# Adafruit_Feather_M0_Adalogger.net
KiCad netlist of a schematic drawn in EAGLE
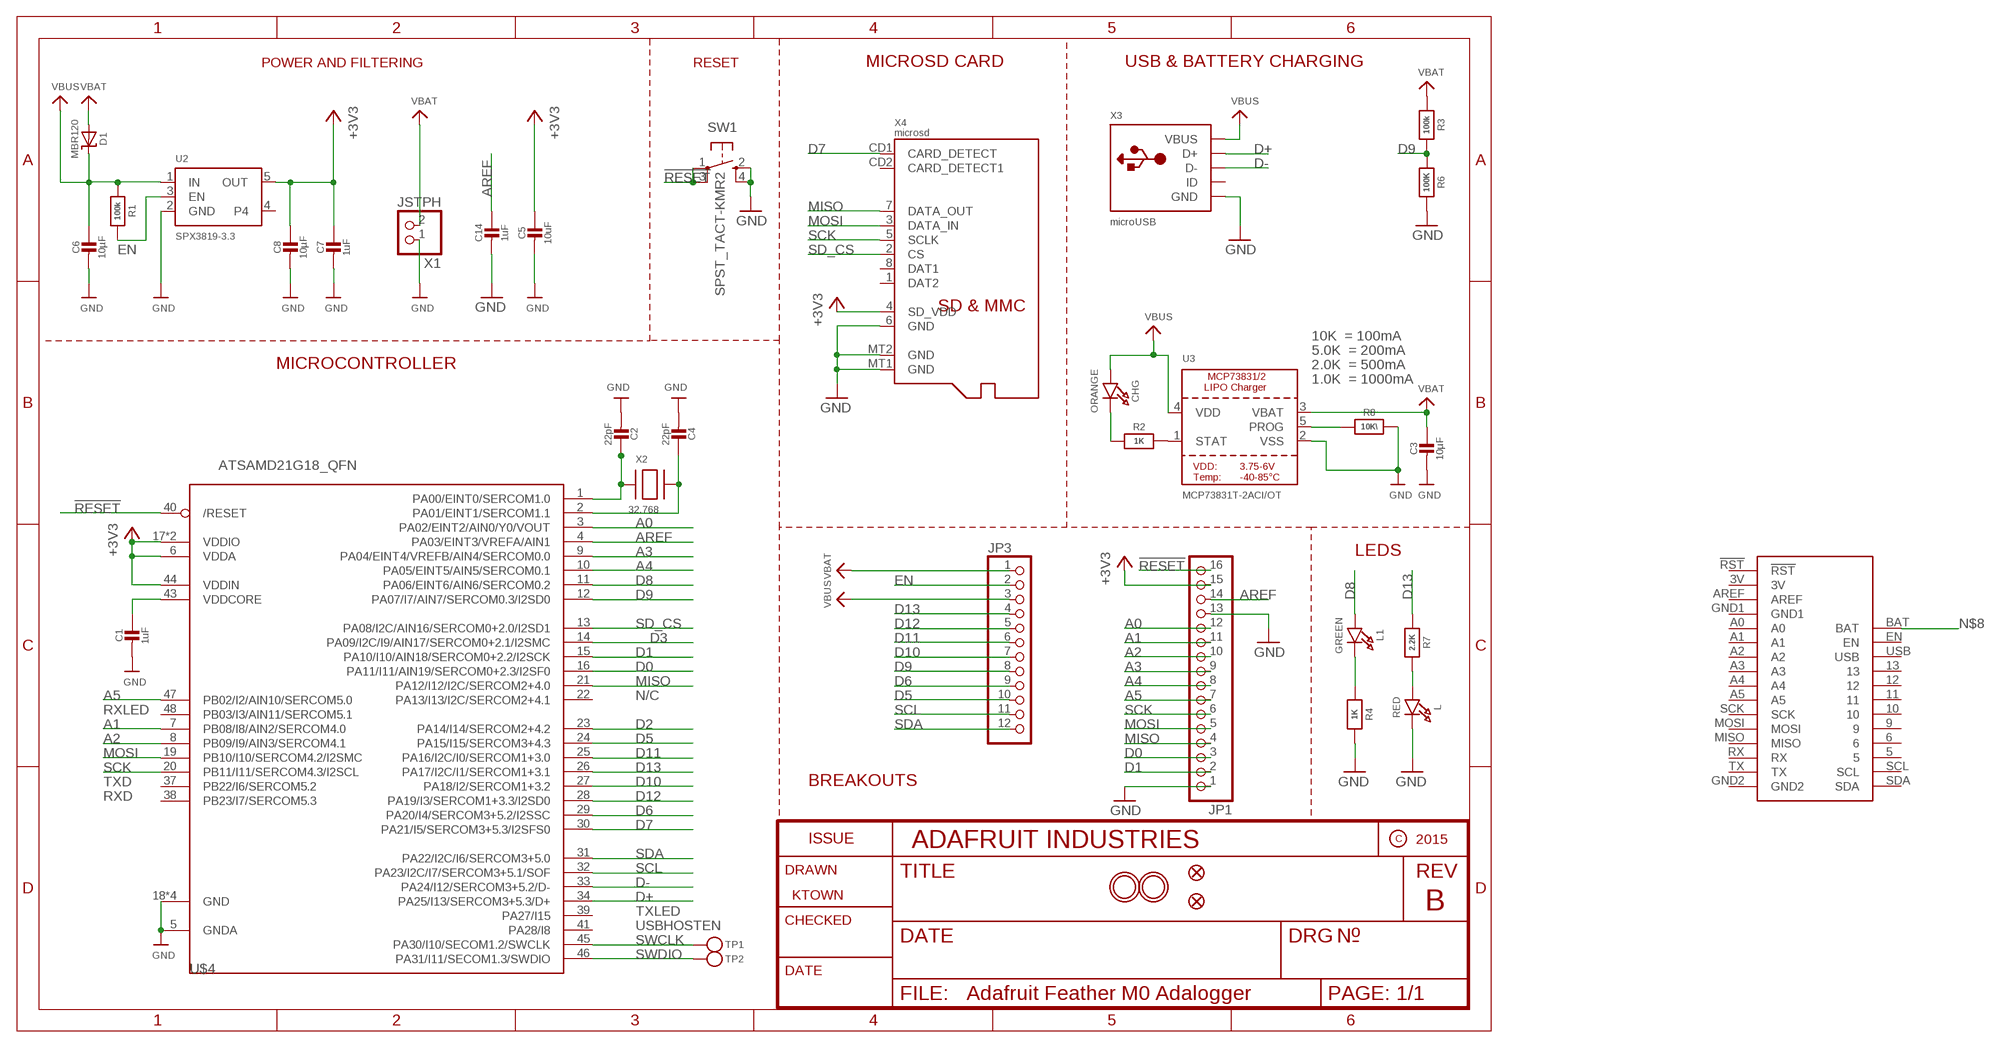
[diagram p0: schematic, sheet 1]

(export (version "E")
  (design (tool "Eeschema 10.0.6"))
  (components
    (comp (ref "C1")
      (value "1uF")
      (footprint "eagle-import:0603-NO")
      (libsource (lib "eagle-import") (part "CAP_CERAMIC0603_NO"))
    )
    (comp (ref "C2")
      (value "22pF")
      (footprint "eagle-import:0603-NO")
      (libsource (lib "eagle-import") (part "CAP_CERAMIC0603_NO"))
    )
    (comp (ref "C3")
      (value "10µF")
      (footprint "eagle-import:0805-NO")
      (libsource (lib "eagle-import") (part "CAP_CERAMIC0805-NOOUTLINE"))
    )
    (comp (ref "C4")
      (value "22pF")
      (footprint "eagle-import:0603-NO")
      (libsource (lib "eagle-import") (part "CAP_CERAMIC0603_NO"))
    )
    (comp (ref "C5")
      (value "10uF")
      (footprint "eagle-import:0805-NO")
      (libsource (lib "eagle-import") (part "CAP_CERAMIC0805-NOOUTLINE"))
    )
    (comp (ref "C6")
      (value "10µF")
      (footprint "eagle-import:0805-NO")
      (libsource (lib "eagle-import") (part "CAP_CERAMIC0805-NOOUTLINE"))
    )
    (comp (ref "C7")
      (value "1uF")
      (footprint "eagle-import:0603-NO")
      (libsource (lib "eagle-import") (part "CAP_CERAMIC0603_NO"))
    )
    (comp (ref "C8")
      (value "10µF")
      (footprint "eagle-import:0805-NO")
      (libsource (lib "eagle-import") (part "CAP_CERAMIC0805-NOOUTLINE"))
    )
    (comp (ref "C14")
      (value "1uF")
      (footprint "eagle-import:0603-NO")
      (libsource (lib "eagle-import") (part "CAP_CERAMIC0603_NO"))
    )
    (comp (ref "CHG")
      (value "ORANGE")
      (footprint "eagle-import:CHIPLED_0805_NOOUTLINE")
      (libsource (lib "eagle-import") (part "LED0805_NOOUTLINE"))
    )
    (comp (ref "D1")
      (value "MBR120")
      (footprint "eagle-import:SOD-123")
      (libsource (lib "eagle-import") (part "DIODE-SCHOTTKYSOD-123"))
    )
    (comp (ref "JP1")
      (value "HEADER-1X16ROUND")
      (footprint "eagle-import:1X16_ROUND")
      (libsource (lib "eagle-import") (part "HEADER-1X16ROUND"))
    )
    (comp (ref "JP3")
      (value "HEADER-1X12")
      (footprint "eagle-import:1X12_ROUND")
      (libsource (lib "eagle-import") (part "HEADER-1X12"))
    )
    (comp (ref "L")
      (value "RED")
      (footprint "eagle-import:CHIPLED_0805_NOOUTLINE")
      (libsource (lib "eagle-import") (part "LED0805_NOOUTLINE"))
    )
    (comp (ref "L1")
      (value "GREEN")
      (footprint "eagle-import:CHIPLED_0805_NOOUTLINE")
      (libsource (lib "eagle-import") (part "LED0805_NOOUTLINE"))
    )
    (comp (ref "R1")
      (value "100k")
      (footprint "eagle-import:0603-NO")
      (libsource (lib "eagle-import") (part "RESISTOR_0603_NOOUT"))
    )
    (comp (ref "R2")
      (value "1K")
      (footprint "eagle-import:0603-NO")
      (libsource (lib "eagle-import") (part "RESISTOR_0603_NOOUT"))
    )
    (comp (ref "R3")
      (value "100k")
      (footprint "eagle-import:0603-NO")
      (libsource (lib "eagle-import") (part "RESISTOR_0603_NOOUT"))
    )
    (comp (ref "R4")
      (value "1K")
      (footprint "eagle-import:0603-NO")
      (libsource (lib "eagle-import") (part "RESISTOR_0603_NOOUT"))
    )
    (comp (ref "R6")
      (value "100K")
      (footprint "eagle-import:0603-NO")
      (libsource (lib "eagle-import") (part "RESISTOR_0603_NOOUT"))
    )
    (comp (ref "R7")
      (value "2.2K")
      (footprint "eagle-import:0603-NO")
      (libsource (lib "eagle-import") (part "RESISTOR_0603_NOOUT"))
    )
    (comp (ref "R8")
      (value "10K\\")
      (footprint "eagle-import:0603-NO")
      (libsource (lib "eagle-import") (part "RESISTOR_0603_NOOUT"))
    )
    (comp (ref "SW1")
      (value "SPST_TACT-KMR2")
      (footprint "eagle-import:KMR2")
      (libsource (lib "eagle-import") (part "SPST_TACT-KMR2"))
    )
    (comp (ref "TP1")
      (value "TESTPOINTROUND1.5MM")
      (footprint "eagle-import:TESTPOINT_ROUND_1.5MM")
      (libsource (lib "eagle-import") (part "TESTPOINTROUND1.5MM"))
    )
    (comp (ref "TP2")
      (value "TESTPOINTROUND1.5MM")
      (footprint "eagle-import:TESTPOINT_ROUND_1.5MM")
      (libsource (lib "eagle-import") (part "TESTPOINTROUND1.5MM"))
    )
    (comp (ref "U$4")
      (value "ATSAMD21G18_QFN")
      (footprint "eagle-import:TQFN48_7MM")
      (libsource (lib "eagle-import") (part "ATSAMD21J_QFN"))
    )
    (comp (ref "U$12")
      (value "FEATHER_MO_ADALOGGER")
      (footprint "eagle-import:FEATHER_M0_ADALOGGER")
      (libsource (lib "eagle-import") (part "FEATHER_MO_ADALOGGER"))
    )
    (comp (ref "U$31")
      (value "MOUNTINGHOLE2.5")
      (footprint "eagle-import:MOUNTINGHOLE_2.5_PLATED")
      (libsource (lib "eagle-import") (part "MOUNTINGHOLE2.5"))
    )
    (comp (ref "U$32")
      (value "MOUNTINGHOLE2.5")
      (footprint "eagle-import:MOUNTINGHOLE_2.5_PLATED")
      (libsource (lib "eagle-import") (part "MOUNTINGHOLE2.5"))
    )
    (comp (ref "U$34")
      (value "FIDUCIAL\"\"")
      (footprint "eagle-import:FIDUCIAL_1MM")
      (libsource (lib "eagle-import") (part "FIDUCIAL{dblquote}{dblquote}"))
    )
    (comp (ref "U$35")
      (value "FIDUCIAL\"\"")
      (footprint "eagle-import:FIDUCIAL_1MM")
      (libsource (lib "eagle-import") (part "FIDUCIAL{dblquote}{dblquote}"))
    )
    (comp (ref "U2")
      (value "SPX3819-3.3")
      (footprint "eagle-import:SOT23-5")
      (libsource (lib "eagle-import") (part "VREG_SOT23-5"))
    )
    (comp (ref "U3")
      (value "MCP73831T-2ACI/OT")
      (footprint "eagle-import:SOT23-5")
      (libsource (lib "eagle-import") (part "MCP73831/2"))
    )
    (comp (ref "X1")
      (value "JSTPH")
      (footprint "eagle-import:JSTPH2")
      (libsource (lib "eagle-import") (part "CON_JST_PH_2PIN"))
    )
    (comp (ref "X2")
      (value "32.768")
      (footprint "eagle-import:XTAL3215")
      (libsource (lib "eagle-import") (part "XTAL-3.2X1.5"))
    )
    (comp (ref "X3")
      (value "microUSB")
      (footprint "eagle-import:4UCONN_20329_V2")
      (libsource (lib "eagle-import") (part "USB_MICRO_20329_V2"))
    )
    (comp (ref "X4")
      (value "microsd")
      (footprint "eagle-import:MICROSD")
      (libsource (lib "eagle-import") (part "MICROSD"))
    )
  )
  (nets
    (net (code "1") (name "+3V3") (class "Default")
      (node (ref "C5") (pin "1") (pinfunction "1_1") (pintype "passive"))
      (node (ref "C7") (pin "1") (pinfunction "1_1") (pintype "passive"))
      (node (ref "C8") (pin "1") (pinfunction "1_1") (pintype "passive"))
      (node (ref "JP1") (pin "15") (pinfunction "15_15") (pintype "passive"))
      (node (ref "U$4") (pin "17") (pinfunction "VDDIO_17") (pintype "power_in"))
      (node (ref "U$4") (pin "36") (pinfunction "VDDIO_36") (pintype "power_in"))
      (node (ref "U$4") (pin "44") (pinfunction "VDDIN_44") (pintype "power_in"))
      (node (ref "U$4") (pin "6") (pinfunction "VDDA_6") (pintype "power_in"))
      (node (ref "U2") (pin "5") (pinfunction "OUT_5") (pintype "power_in"))
      (node (ref "X4") (pin "4") (pinfunction "SD_VDD_4") (pintype "power_in"))
    )
    (net (code "2") (name "/A0") (class "Default")
      (node (ref "JP1") (pin "12") (pinfunction "12_12") (pintype "passive"))
      (node (ref "U$4") (pin "3") (pinfunction "PA02/EINT2/AIN0/Y0/VOUT_3") (pintype "bidirectional"))
    )
    (net (code "3") (name "/A1") (class "Default")
      (node (ref "JP1") (pin "11") (pinfunction "11_11") (pintype "passive"))
      (node (ref "U$4") (pin "7") (pinfunction "PB08/I8/AIN2/SERCOM4.0_7") (pintype "bidirectional"))
    )
    (net (code "4") (name "/A2") (class "Default")
      (node (ref "JP1") (pin "10") (pinfunction "10_10") (pintype "passive"))
      (node (ref "U$4") (pin "8") (pinfunction "PB09/I9/AIN3/SERCOM4.1_8") (pintype "bidirectional"))
    )
    (net (code "5") (name "/A3") (class "Default")
      (node (ref "JP1") (pin "9") (pinfunction "9_9") (pintype "passive"))
      (node (ref "U$4") (pin "9") (pinfunction "PA04/EINT4/VREFB/AIN4/SERCOM0.0_9") (pintype "bidirectional"))
    )
    (net (code "6") (name "/A4") (class "Default")
      (node (ref "JP1") (pin "8") (pinfunction "8_8") (pintype "passive"))
      (node (ref "U$4") (pin "10") (pinfunction "PA05/EINT5/AIN5/SERCOM0.1_10") (pintype "bidirectional"))
    )
    (net (code "7") (name "/A5") (class "Default")
      (node (ref "JP1") (pin "7") (pinfunction "7_7") (pintype "passive"))
      (node (ref "U$4") (pin "47") (pinfunction "PB02/I2/AIN10/SERCOM5.0_47") (pintype "bidirectional"))
    )
    (net (code "8") (name "/AREF") (class "Default")
      (node (ref "C14") (pin "1") (pinfunction "1_1") (pintype "passive"))
      (node (ref "JP1") (pin "14") (pinfunction "14_14") (pintype "passive"))
      (node (ref "U$4") (pin "4") (pinfunction "PA03/EINT3/VREFA/AIN1_4") (pintype "bidirectional"))
    )
    (net (code "9") (name "/D+") (class "Default")
      (node (ref "U$4") (pin "34") (pinfunction "PA25/I13/SERCOM3+5.3/D+_34") (pintype "bidirectional"))
      (node (ref "X3") (pin "D+") (pinfunction "D+_D+") (pintype "bidirectional"))
    )
    (net (code "10") (name "/D-") (class "Default")
      (node (ref "U$4") (pin "33") (pinfunction "PA24/I12/SERCOM3+5.2/D-_33") (pintype "bidirectional"))
      (node (ref "X3") (pin "D-") (pinfunction "D-_D-") (pintype "bidirectional"))
    )
    (net (code "11") (name "/D0") (class "Default")
      (node (ref "JP1") (pin "3") (pinfunction "3_3") (pintype "passive"))
      (node (ref "U$4") (pin "16") (pinfunction "PA11/I11/AIN19/SERCOM0+2.3/I2SF0_16") (pintype "bidirectional"))
    )
    (net (code "12") (name "/D1") (class "Default")
      (node (ref "JP1") (pin "2") (pinfunction "2_2") (pintype "passive"))
      (node (ref "U$4") (pin "15") (pinfunction "PA10/I10/AIN18/SERCOM0+2.2/I2SCK_15") (pintype "bidirectional"))
    )
    (net (code "13") (name "/D2") (class "Default")
      (node (ref "U$4") (pin "23") (pinfunction "PA14/I14/SERCOM2+4.2_23") (pintype "bidirectional"))
    )
    (net (code "14") (name "/D3") (class "Default")
      (node (ref "U$4") (pin "14") (pinfunction "PA09/I2C/I9/AIN17/SERCOM0+2.1/I2SMC_14") (pintype "bidirectional"))
    )
    (net (code "15") (name "/D5") (class "Default")
      (node (ref "JP3") (pin "10") (pinfunction "10_10") (pintype "passive"))
      (node (ref "U$4") (pin "24") (pinfunction "PA15/I15/SERCOM3+4.3_24") (pintype "bidirectional"))
    )
    (net (code "16") (name "/D6") (class "Default")
      (node (ref "JP3") (pin "9") (pinfunction "9_9") (pintype "passive"))
      (node (ref "U$4") (pin "29") (pinfunction "PA20/I4/SERCOM3+5.2/I2SSC_29") (pintype "bidirectional"))
    )
    (net (code "17") (name "/D7") (class "Default")
      (node (ref "U$4") (pin "30") (pinfunction "PA21/I5/SERCOM3+5.3/I2SFS0_30") (pintype "bidirectional"))
      (node (ref "X4") (pin "CD1") (pinfunction "CARD_DETECT_CD1") (pintype "passive"))
    )
    (net (code "18") (name "/D8") (class "Default")
      (node (ref "L1") (pin "A") (pinfunction "A_A") (pintype "passive"))
      (node (ref "U$4") (pin "11") (pinfunction "PA06/EINT6/AIN6/SERCOM0.2_11") (pintype "bidirectional"))
    )
    (net (code "19") (name "/D9") (class "Default")
      (node (ref "JP3") (pin "8") (pinfunction "8_8") (pintype "passive"))
      (node (ref "R3") (pin "2") (pinfunction "2_2") (pintype "passive"))
      (node (ref "R6") (pin "1") (pinfunction "1_1") (pintype "passive"))
      (node (ref "U$4") (pin "12") (pinfunction "PA07/I7/AIN7/SERCOM0.3/I2SD0_12") (pintype "bidirectional"))
    )
    (net (code "20") (name "/D10") (class "Default")
      (node (ref "JP3") (pin "7") (pinfunction "7_7") (pintype "passive"))
      (node (ref "U$4") (pin "27") (pinfunction "PA18/I2/SERCOM1+3.2_27") (pintype "bidirectional"))
    )
    (net (code "21") (name "/D11") (class "Default")
      (node (ref "JP3") (pin "6") (pinfunction "6_6") (pintype "passive"))
      (node (ref "U$4") (pin "25") (pinfunction "PA16/I2C/I0/SERCOM1+3.0_25") (pintype "bidirectional"))
    )
    (net (code "22") (name "/D12") (class "Default")
      (node (ref "JP3") (pin "5") (pinfunction "5_5") (pintype "passive"))
      (node (ref "U$4") (pin "28") (pinfunction "PA19/I3/SERCOM1+3.3/I2SD0_28") (pintype "bidirectional"))
    )
    (net (code "23") (name "/D13") (class "Default")
      (node (ref "JP3") (pin "4") (pinfunction "4_4") (pintype "passive"))
      (node (ref "R7") (pin "1") (pinfunction "1_1") (pintype "passive"))
      (node (ref "U$4") (pin "26") (pinfunction "PA17/I2C/I1/SERCOM1+3.1_26") (pintype "bidirectional"))
    )
    (net (code "24") (name "/EN") (class "Default")
      (node (ref "JP3") (pin "2") (pinfunction "2_2") (pintype "passive"))
      (node (ref "R1") (pin "2") (pinfunction "2_2") (pintype "passive"))
      (node (ref "U2") (pin "3") (pinfunction "EN_3") (pintype "input"))
    )
    (net (code "25") (name "/MISO") (class "Default")
      (node (ref "JP1") (pin "4") (pinfunction "4_4") (pintype "passive"))
      (node (ref "U$4") (pin "21") (pinfunction "PA12/I12/I2C/SERCOM2+4.0_21") (pintype "bidirectional"))
      (node (ref "X4") (pin "7") (pinfunction "DATA_OUT_7") (pintype "output"))
    )
    (net (code "26") (name "/MOSI") (class "Default")
      (node (ref "JP1") (pin "5") (pinfunction "5_5") (pintype "passive"))
      (node (ref "U$4") (pin "19") (pinfunction "PB10/I10/SERCOM4.2/I2SMC_19") (pintype "bidirectional"))
      (node (ref "X4") (pin "3") (pinfunction "DATA_IN_3") (pintype "input"))
    )
    (net (code "27") (name "/N$8") (class "Default")
      (node (ref "U$12") (pin "BAT") (pinfunction "BAT_BAT") (pintype "bidirectional"))
    )
    (net (code "28") (name "/SCK") (class "Default")
      (node (ref "JP1") (pin "6") (pinfunction "6_6") (pintype "passive"))
      (node (ref "U$4") (pin "20") (pinfunction "PB11/I11/SERCOM4.3/I2SCL_20") (pintype "bidirectional"))
      (node (ref "X4") (pin "5") (pinfunction "SCLK_5") (pintype "input"))
    )
    (net (code "29") (name "/SCL") (class "Default")
      (node (ref "JP3") (pin "11") (pinfunction "11_11") (pintype "passive"))
      (node (ref "U$4") (pin "32") (pinfunction "PA23/I2C/I7/SERCOM3+5.1/SOF_32") (pintype "bidirectional"))
    )
    (net (code "30") (name "/SDA") (class "Default")
      (node (ref "JP3") (pin "12") (pinfunction "12_12") (pintype "passive"))
      (node (ref "U$4") (pin "31") (pinfunction "PA22/I2C/I6/SERCOM3+5.0_31") (pintype "bidirectional"))
    )
    (net (code "31") (name "/SD_CS") (class "Default")
      (node (ref "U$4") (pin "13") (pinfunction "PA08/I2C/AIN16/SERCOM0+2.0/I2SD1_13") (pintype "bidirectional"))
      (node (ref "X4") (pin "2") (pinfunction "CS_2") (pintype "input"))
    )
    (net (code "32") (name "/SWCLK") (class "Default")
      (node (ref "TP1") (pin "P$1") (pinfunction "P$1_P$1") (pintype "bidirectional"))
      (node (ref "U$4") (pin "45") (pinfunction "PA30/I10/SECOM1.2/SWCLK_45") (pintype "bidirectional"))
    )
    (net (code "33") (name "/SWDIO") (class "Default")
      (node (ref "TP2") (pin "P$1") (pinfunction "P$1_P$1") (pintype "bidirectional"))
      (node (ref "U$4") (pin "46") (pinfunction "PA31/I11/SECOM1.3/SWDIO_46") (pintype "bidirectional"))
    )
    (net (code "34") (name "/~{RESET}") (class "Default")
      (node (ref "JP1") (pin "16") (pinfunction "16_16") (pintype "passive"))
      (node (ref "SW1") (pin "1") (pinfunction "P_1") (pintype "passive"))
      (node (ref "SW1") (pin "3") (pinfunction "P1_3") (pintype "passive"))
      (node (ref "U$4") (pin "40") (pinfunction "/RESET_40") (pintype "bidirectional"))
    )
    (net (code "35") (name "GND") (class "Default")
      (node (ref "C1") (pin "2") (pinfunction "2_2") (pintype "passive"))
      (node (ref "C14") (pin "2") (pinfunction "2_2") (pintype "passive"))
      (node (ref "C2") (pin "2") (pinfunction "2_2") (pintype "passive"))
      (node (ref "C3") (pin "2") (pinfunction "2_2") (pintype "passive"))
      (node (ref "C4") (pin "2") (pinfunction "2_2") (pintype "passive"))
      (node (ref "C5") (pin "2") (pinfunction "2_2") (pintype "passive"))
      (node (ref "C6") (pin "2") (pinfunction "2_2") (pintype "passive"))
      (node (ref "C7") (pin "2") (pinfunction "2_2") (pintype "passive"))
      (node (ref "C8") (pin "2") (pinfunction "2_2") (pintype "passive"))
      (node (ref "JP1") (pin "1") (pinfunction "1_1") (pintype "passive"))
      (node (ref "JP1") (pin "13") (pinfunction "13_13") (pintype "passive"))
      (node (ref "L") (pin "C") (pinfunction "C_C") (pintype "passive"))
      (node (ref "R4") (pin "2") (pinfunction "2_2") (pintype "passive"))
      (node (ref "R6") (pin "2") (pinfunction "2_2") (pintype "passive"))
      (node (ref "R8") (pin "2") (pinfunction "2_2") (pintype "passive"))
      (node (ref "SW1") (pin "2") (pinfunction "S_2") (pintype "passive"))
      (node (ref "SW1") (pin "4") (pinfunction "S1_4") (pintype "passive"))
      (node (ref "U$4") (pin "18") (pinfunction "GND_18") (pintype "power_in"))
      (node (ref "U$4") (pin "35") (pinfunction "GND_35") (pintype "power_in"))
      (node (ref "U$4") (pin "42") (pinfunction "GND_42") (pintype "power_in"))
      (node (ref "U$4") (pin "5") (pinfunction "GNDA_5") (pintype "power_in"))
      (node (ref "U$4") (pin "THERMAL") (pinfunction "GND_THERMAL") (pintype "power_in"))
      (node (ref "U2") (pin "2") (pinfunction "GND_2") (pintype "power_in"))
      (node (ref "U3") (pin "2") (pinfunction "VSS_2") (pintype "power_in"))
      (node (ref "X1") (pin "1") (pinfunction "1_1") (pintype "passive"))
      (node (ref "X3") (pin "BASE@1") (pinfunction "GND_BASE@1") (pintype "power_in"))
      (node (ref "X3") (pin "BASE@2") (pinfunction "GND_BASE@2") (pintype "power_in"))
      (node (ref "X3") (pin "GND") (pinfunction "GND_GND") (pintype "power_in"))
      (node (ref "X3") (pin "SPRT@1") (pinfunction "GND_SPRT@1") (pintype "power_in"))
      (node (ref "X3") (pin "SPRT@2") (pinfunction "GND_SPRT@2") (pintype "power_in"))
      (node (ref "X3") (pin "SPRT@3") (pinfunction "GND_SPRT@3") (pintype "power_in"))
      (node (ref "X3") (pin "SPRT@4") (pinfunction "GND_SPRT@4") (pintype "power_in"))
      (node (ref "X4") (pin "6") (pinfunction "GND_6") (pintype "power_in"))
      (node (ref "X4") (pin "MT1") (pinfunction "GND_MT1") (pintype "power_in"))
      (node (ref "X4") (pin "MT2") (pinfunction "GND_MT2") (pintype "power_in"))
    )
    (net (code "36") (name "Net-(CHG-PadC)") (class "Default")
      (node (ref "CHG") (pin "C") (pinfunction "C_C") (pintype "passive"))
      (node (ref "R2") (pin "1") (pinfunction "1_1") (pintype "passive"))
    )
    (net (code "37") (name "Net-(L-PadA)") (class "Default")
      (node (ref "L") (pin "A") (pinfunction "A_A") (pintype "passive"))
      (node (ref "R7") (pin "2") (pinfunction "2_2") (pintype "passive"))
    )
    (net (code "38") (name "Net-(L1-PadC)") (class "Default")
      (node (ref "L1") (pin "C") (pinfunction "C_C") (pintype "passive"))
      (node (ref "R4") (pin "1") (pinfunction "1_1") (pintype "passive"))
    )
    (net (code "39") (name "Net-(U$4-PA00{slash}EINT0{slash}SERCOM1.0)") (class "Default")
      (node (ref "C2") (pin "1") (pinfunction "1_1") (pintype "passive"))
      (node (ref "U$4") (pin "1") (pinfunction "PA00/EINT0/SERCOM1.0_1") (pintype "bidirectional"))
      (node (ref "X2") (pin "P$1") (pinfunction "P$1_P$1") (pintype "bidirectional"))
    )
    (net (code "40") (name "Net-(U$4-PA01{slash}EINT1{slash}SERCOM1.1)") (class "Default")
      (node (ref "C4") (pin "1") (pinfunction "1_1") (pintype "passive"))
      (node (ref "U$4") (pin "2") (pinfunction "PA01/EINT1/SERCOM1.1_2") (pintype "bidirectional"))
      (node (ref "X2") (pin "P$2") (pinfunction "P$2_P$2") (pintype "bidirectional"))
    )
    (net (code "41") (name "Net-(U$4-VDDCORE)") (class "Default")
      (node (ref "C1") (pin "1") (pinfunction "1_1") (pintype "passive"))
      (node (ref "U$4") (pin "43") (pinfunction "VDDCORE_43") (pintype "power_in"))
    )
    (net (code "42") (name "Net-(U3-PROG)") (class "Default")
      (node (ref "R8") (pin "1") (pinfunction "1_1") (pintype "passive"))
      (node (ref "U3") (pin "5") (pinfunction "PROG_5") (pintype "input"))
    )
    (net (code "43") (name "Net-(U3-STAT)") (class "Default")
      (node (ref "R2") (pin "2") (pinfunction "2_2") (pintype "passive"))
      (node (ref "U3") (pin "1") (pinfunction "STAT_1") (pintype "output"))
    )
    (net (code "44") (name "VBAT") (class "Default")
      (node (ref "C3") (pin "1") (pinfunction "1_1") (pintype "passive"))
      (node (ref "D1") (pin "A") (pinfunction "A_A") (pintype "passive"))
      (node (ref "JP3") (pin "1") (pinfunction "1_1") (pintype "passive"))
      (node (ref "R3") (pin "1") (pinfunction "1_1") (pintype "passive"))
      (node (ref "U3") (pin "3") (pinfunction "VBAT_3") (pintype "power_in"))
      (node (ref "X1") (pin "2") (pinfunction "2_2") (pintype "passive"))
    )
    (net (code "45") (name "VBUS") (class "Default")
      (node (ref "C6") (pin "1") (pinfunction "1_1") (pintype "passive"))
      (node (ref "CHG") (pin "A") (pinfunction "A_A") (pintype "passive"))
      (node (ref "D1") (pin "C") (pinfunction "C_C") (pintype "passive"))
      (node (ref "JP3") (pin "3") (pinfunction "3_3") (pintype "passive"))
      (node (ref "R1") (pin "1") (pinfunction "1_1") (pintype "passive"))
      (node (ref "U2") (pin "1") (pinfunction "IN_1") (pintype "power_in"))
      (node (ref "U3") (pin "4") (pinfunction "VDD_4") (pintype "power_in"))
      (node (ref "X3") (pin "VBUS") (pinfunction "VBUS_VBUS") (pintype "power_in"))
    )
    (net (code "46") (name "unconnected-(U$4-PA13{slash}I13{slash}I2C{slash}SERCOM2+4.1-Pad22)") (class "Default")
      (node (ref "U$4") (pin "22") (pinfunction "PA13/I13/I2C/SERCOM2+4.1_22") (pintype "bidirectional"))
    )
    (net (code "47") (name "unconnected-(U$4-PA27{slash}I15-Pad39)") (class "Default")
      (node (ref "U$4") (pin "39") (pinfunction "PA27/I15_39") (pintype "bidirectional"))
    )
    (net (code "48") (name "unconnected-(U$4-PA28{slash}I8-Pad41)") (class "Default")
      (node (ref "U$4") (pin "41") (pinfunction "PA28/I8_41") (pintype "bidirectional"))
    )
    (net (code "49") (name "unconnected-(U$4-PB03{slash}I3{slash}AIN11{slash}SERCOM5.1-Pad48)") (class "Default")
      (node (ref "U$4") (pin "48") (pinfunction "PB03/I3/AIN11/SERCOM5.1_48") (pintype "bidirectional"))
    )
    (net (code "50") (name "unconnected-(U$4-PB22{slash}I6{slash}SERCOM5.2-Pad37)") (class "Default")
      (node (ref "U$4") (pin "37") (pinfunction "PB22/I6/SERCOM5.2_37") (pintype "bidirectional"))
    )
    (net (code "51") (name "unconnected-(U$4-PB23{slash}I7{slash}SERCOM5.3-Pad38)") (class "Default")
      (node (ref "U$4") (pin "38") (pinfunction "PB23/I7/SERCOM5.3_38") (pintype "bidirectional"))
    )
    (net (code "52") (name "unconnected-(U$12-Pad3V)") (class "Default")
      (node (ref "U$12") (pin "3V") (pinfunction "3V_3V") (pintype "bidirectional"))
    )
    (net (code "53") (name "unconnected-(U$12-Pad5)") (class "Default")
      (node (ref "U$12") (pin "5") (pinfunction "5_5") (pintype "bidirectional"))
    )
    (net (code "54") (name "unconnected-(U$12-Pad6)") (class "Default")
      (node (ref "U$12") (pin "6") (pinfunction "6_6") (pintype "bidirectional"))
    )
    (net (code "55") (name "unconnected-(U$12-Pad9)") (class "Default")
      (node (ref "U$12") (pin "9") (pinfunction "9_9") (pintype "bidirectional"))
    )
    (net (code "56") (name "unconnected-(U$12-Pad10)") (class "Default")
      (node (ref "U$12") (pin "10") (pinfunction "10_10") (pintype "bidirectional"))
    )
    (net (code "57") (name "unconnected-(U$12-Pad11)") (class "Default")
      (node (ref "U$12") (pin "11") (pinfunction "11_11") (pintype "bidirectional"))
    )
    (net (code "58") (name "unconnected-(U$12-Pad12)") (class "Default")
      (node (ref "U$12") (pin "12") (pinfunction "12_12") (pintype "bidirectional"))
    )
    (net (code "59") (name "unconnected-(U$12-Pad13)") (class "Default")
      (node (ref "U$12") (pin "13") (pinfunction "13_13") (pintype "bidirectional"))
    )
    (net (code "60") (name "unconnected-(U$12-PadA0)") (class "Default")
      (node (ref "U$12") (pin "A0") (pinfunction "A0_A0") (pintype "bidirectional"))
    )
    (net (code "61") (name "unconnected-(U$12-PadA1)") (class "Default")
      (node (ref "U$12") (pin "A1") (pinfunction "A1_A1") (pintype "bidirectional"))
    )
    (net (code "62") (name "unconnected-(U$12-PadA2)") (class "Default")
      (node (ref "U$12") (pin "A2") (pinfunction "A2_A2") (pintype "bidirectional"))
    )
    (net (code "63") (name "unconnected-(U$12-PadA3)") (class "Default")
      (node (ref "U$12") (pin "A3") (pinfunction "A3_A3") (pintype "bidirectional"))
    )
    (net (code "64") (name "unconnected-(U$12-PadA4)") (class "Default")
      (node (ref "U$12") (pin "A4") (pinfunction "A4_A4") (pintype "bidirectional"))
    )
    (net (code "65") (name "unconnected-(U$12-PadA5)") (class "Default")
      (node (ref "U$12") (pin "A5") (pinfunction "A5_A5") (pintype "bidirectional"))
    )
    (net (code "66") (name "unconnected-(U$12-PadAREF)") (class "Default")
      (node (ref "U$12") (pin "AREF") (pinfunction "AREF_AREF") (pintype "bidirectional"))
    )
    (net (code "67") (name "unconnected-(U$12-PadEN)") (class "Default")
      (node (ref "U$12") (pin "EN") (pinfunction "EN_EN") (pintype "bidirectional"))
    )
    (net (code "68") (name "unconnected-(U$12-PadGND1)") (class "Default")
      (node (ref "U$12") (pin "GND1") (pinfunction "GND1_GND1") (pintype "bidirectional"))
    )
    (net (code "69") (name "unconnected-(U$12-PadGND2)") (class "Default")
      (node (ref "U$12") (pin "GND2") (pinfunction "GND2_GND2") (pintype "bidirectional"))
    )
    (net (code "70") (name "unconnected-(U$12-PadMISO)") (class "Default")
      (node (ref "U$12") (pin "MISO") (pinfunction "MISO_MISO") (pintype "bidirectional"))
    )
    (net (code "71") (name "unconnected-(U$12-PadMOSI)") (class "Default")
      (node (ref "U$12") (pin "MOSI") (pinfunction "MOSI_MOSI") (pintype "bidirectional"))
    )
    (net (code "72") (name "unconnected-(U$12-PadRX)") (class "Default")
      (node (ref "U$12") (pin "RX") (pinfunction "RX_RX") (pintype "bidirectional"))
    )
    (net (code "73") (name "unconnected-(U$12-PadSCK)") (class "Default")
      (node (ref "U$12") (pin "SCK") (pinfunction "SCK_SCK") (pintype "bidirectional"))
    )
    (net (code "74") (name "unconnected-(U$12-PadSCL)") (class "Default")
      (node (ref "U$12") (pin "SCL") (pinfunction "SCL_SCL") (pintype "bidirectional"))
    )
    (net (code "75") (name "unconnected-(U$12-PadSDA)") (class "Default")
      (node (ref "U$12") (pin "SDA") (pinfunction "SDA_SDA") (pintype "bidirectional"))
    )
    (net (code "76") (name "unconnected-(U$12-PadTX)") (class "Default")
      (node (ref "U$12") (pin "TX") (pinfunction "TX_TX") (pintype "bidirectional"))
    )
    (net (code "77") (name "unconnected-(U$12-PadUSB)") (class "Default")
      (node (ref "U$12") (pin "USB") (pinfunction "USB_USB") (pintype "bidirectional"))
    )
    (net (code "78") (name "unconnected-(U$12-~{RST}-Pad!RST)") (class "Default")
      (node (ref "U$12") (pin "!RST") (pinfunction "~{RST}_!RST") (pintype "bidirectional"))
    )
    (net (code "79") (name "unconnected-(U2-P4-Pad4)") (class "Default")
      (node (ref "U2") (pin "4") (pinfunction "P4_4") (pintype "bidirectional"))
    )
    (net (code "80") (name "unconnected-(X3-PadID)") (class "Default")
      (node (ref "X3") (pin "ID") (pinfunction "ID_ID") (pintype "bidirectional"))
    )
    (net (code "81") (name "unconnected-(X4-CARD_DETECT1-PadCD2)") (class "Default")
      (node (ref "X4") (pin "CD2") (pinfunction "CARD_DETECT1_CD2") (pintype "passive"))
    )
    (net (code "82") (name "unconnected-(X4-DAT1-Pad8)") (class "Default")
      (node (ref "X4") (pin "8") (pinfunction "DAT1_8") (pintype "bidirectional"))
    )
    (net (code "83") (name "unconnected-(X4-DAT2-Pad1)") (class "Default")
      (node (ref "X4") (pin "1") (pinfunction "DAT2_1") (pintype "bidirectional"))
    )
  )
)
